# Esquema.net
KiCad netlist of a schematic drawn in EAGLE
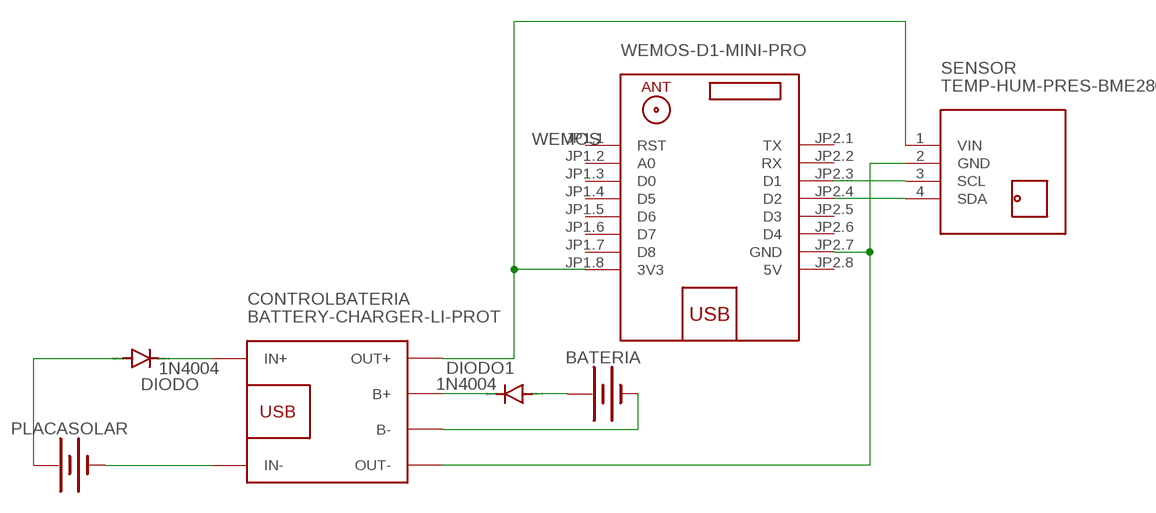
[diagram p0: schematic, sheet 1]

(export (version "E")
  (design (tool "Eeschema 10.0.6"))
  (components
    (comp (ref "BATERIA")
      (value "BATTERY-18650")
      (footprint "eagle-import:BATTERY_18650-HOLDER")
      (libsource (lib "eagle-import") (part "BATTERY-18650"))
    )
    (comp (ref "CONTROLBATERIA")
      (value "BATTERY-CHARGER-LI-PROT")
      (footprint "eagle-import:BATTERY-CHARGER-LI-PROT")
      (libsource (lib "eagle-import") (part "BATTERY-CHARGER-LI-PROT"))
    )
    (comp (ref "DIODO")
      (value "1N4004")
      (footprint "eagle-import:DO41-10")
      (libsource (lib "eagle-import") (part "1N4004"))
    )
    (comp (ref "DIODO1")
      (value "1N4004")
      (footprint "eagle-import:DO41-10")
      (libsource (lib "eagle-import") (part "1N4004"))
    )
    (comp (ref "PLACASOLAR")
      (value "BATTERY-20MM_SMD")
      (footprint "eagle-import:BATTCON_20MM")
      (libsource (lib "eagle-import") (part "BATTERY-20MM_SMD"))
    )
    (comp (ref "SENSOR")
      (value "TEMP-HUM-PRES-BME280")
      (footprint "eagle-import:TEMP-HUM-PRES-BME280")
      (libsource (lib "eagle-import") (part "TEMP-HUM-PRES-BME280"))
    )
    (comp (ref "WEMOS")
      (value "WEMOS-D1-MINI-PRO")
      (footprint "eagle-import:WEMOS-D1-MINI-PRO")
      (fields (field (name "SPICEPREFIX") "X"))
      (libsource (lib "eagle-import") (part "WEMOS-D1-MINI-PRO"))
    )
  )
  (nets
    (net (code "1") (name "/5V") (class "Default")
      (node (ref "WEMOS") (pin "JP2.8") (pinfunction "5V_JP2.8") (pintype "power_in"))
    )
    (net (code "2") (name "Net-(BATERIA-+)") (class "Default")
      (node (ref "BATERIA") (pin "PWR@1") (pinfunction "+_PWR@1") (pintype "power_in"))
      (node (ref "DIODO1") (pin "A") (pinfunction "A_A") (pintype "passive"))
    )
    (net (code "3") (name "Net-(BATERIA--)") (class "Default")
      (node (ref "BATERIA") (pin "GND@1") (pinfunction "-_GND@1") (pintype "power_in"))
      (node (ref "CONTROLBATERIA") (pin "B-") (pinfunction "B-_B-") (pintype "bidirectional"))
    )
    (net (code "4") (name "Net-(CONTROLBATERIA-PadB+)") (class "Default")
      (node (ref "CONTROLBATERIA") (pin "B+") (pinfunction "B+_B+") (pintype "bidirectional"))
      (node (ref "DIODO1") (pin "C") (pinfunction "C_C") (pintype "passive"))
    )
    (net (code "5") (name "Net-(CONTROLBATERIA-PadIN+)") (class "Default")
      (node (ref "CONTROLBATERIA") (pin "IN+") (pinfunction "IN+_IN+") (pintype "bidirectional"))
      (node (ref "DIODO") (pin "C") (pinfunction "C_C") (pintype "passive"))
    )
    (net (code "6") (name "Net-(PLACASOLAR-+)") (class "Default")
      (node (ref "DIODO") (pin "A") (pinfunction "A_A") (pintype "passive"))
      (node (ref "PLACASOLAR") (pin "1") (pinfunction "+_1") (pintype "power_in"))
    )
    (net (code "7") (name "Net-(PLACASOLAR--)") (class "Default")
      (node (ref "CONTROLBATERIA") (pin "IN-") (pinfunction "IN-_IN-") (pintype "bidirectional"))
      (node (ref "PLACASOLAR") (pin "2") (pinfunction "-_2") (pintype "power_in"))
    )
    (net (code "8") (name "Net-(SENSOR-GND)") (class "Default")
      (node (ref "CONTROLBATERIA") (pin "OUT-") (pinfunction "OUT-_OUT-") (pintype "bidirectional"))
      (node (ref "SENSOR") (pin "2") (pinfunction "GND_2") (pintype "power_in"))
      (node (ref "WEMOS") (pin "JP2.7") (pinfunction "GND_JP2.7") (pintype "power_in"))
    )
    (net (code "9") (name "Net-(SENSOR-SCL)") (class "Default")
      (node (ref "SENSOR") (pin "3") (pinfunction "SCL_3") (pintype "bidirectional"))
      (node (ref "WEMOS") (pin "JP2.3") (pinfunction "D1_JP2.3") (pintype "bidirectional"))
    )
    (net (code "10") (name "Net-(SENSOR-SDA)") (class "Default")
      (node (ref "SENSOR") (pin "4") (pinfunction "SDA_4") (pintype "bidirectional"))
      (node (ref "WEMOS") (pin "JP2.4") (pinfunction "D2_JP2.4") (pintype "bidirectional"))
    )
    (net (code "11") (name "Net-(SENSOR-VIN)") (class "Default")
      (node (ref "CONTROLBATERIA") (pin "OUT+") (pinfunction "OUT+_OUT+") (pintype "bidirectional"))
      (node (ref "SENSOR") (pin "1") (pinfunction "VIN_1") (pintype "power_in"))
      (node (ref "WEMOS") (pin "JP1.8") (pinfunction "3V3_JP1.8") (pintype "power_in"))
    )
    (net (code "12") (name "unconnected-(WEMOS-A0-PadJP1.2)") (class "Default")
      (node (ref "WEMOS") (pin "JP1.2") (pinfunction "A0_JP1.2") (pintype "bidirectional"))
    )
    (net (code "13") (name "unconnected-(WEMOS-D0-PadJP1.3)") (class "Default")
      (node (ref "WEMOS") (pin "JP1.3") (pinfunction "D0_JP1.3") (pintype "bidirectional"))
    )
    (net (code "14") (name "unconnected-(WEMOS-D3-PadJP2.5)") (class "Default")
      (node (ref "WEMOS") (pin "JP2.5") (pinfunction "D3_JP2.5") (pintype "bidirectional"))
    )
    (net (code "15") (name "unconnected-(WEMOS-D4-PadJP2.6)") (class "Default")
      (node (ref "WEMOS") (pin "JP2.6") (pinfunction "D4_JP2.6") (pintype "bidirectional"))
    )
    (net (code "16") (name "unconnected-(WEMOS-D5-PadJP1.4)") (class "Default")
      (node (ref "WEMOS") (pin "JP1.4") (pinfunction "D5_JP1.4") (pintype "bidirectional"))
    )
    (net (code "17") (name "unconnected-(WEMOS-D6-PadJP1.5)") (class "Default")
      (node (ref "WEMOS") (pin "JP1.5") (pinfunction "D6_JP1.5") (pintype "bidirectional"))
    )
    (net (code "18") (name "unconnected-(WEMOS-D7-PadJP1.6)") (class "Default")
      (node (ref "WEMOS") (pin "JP1.6") (pinfunction "D7_JP1.6") (pintype "bidirectional"))
    )
    (net (code "19") (name "unconnected-(WEMOS-D8-PadJP1.7)") (class "Default")
      (node (ref "WEMOS") (pin "JP1.7") (pinfunction "D8_JP1.7") (pintype "bidirectional"))
    )
    (net (code "20") (name "unconnected-(WEMOS-RST-PadJP1.1)") (class "Default")
      (node (ref "WEMOS") (pin "JP1.1") (pinfunction "RST_JP1.1") (pintype "bidirectional"))
    )
    (net (code "21") (name "unconnected-(WEMOS-RX-PadJP2.2)") (class "Default")
      (node (ref "WEMOS") (pin "JP2.2") (pinfunction "RX_JP2.2") (pintype "bidirectional"))
    )
    (net (code "22") (name "unconnected-(WEMOS-TX-PadJP2.1)") (class "Default")
      (node (ref "WEMOS") (pin "JP2.1") (pinfunction "TX_JP2.1") (pintype "bidirectional"))
    )
  )
)
